# Grove_-_Themocouple_Amplifier_MAX31850K.net
KiCad netlist of a schematic drawn in EAGLE
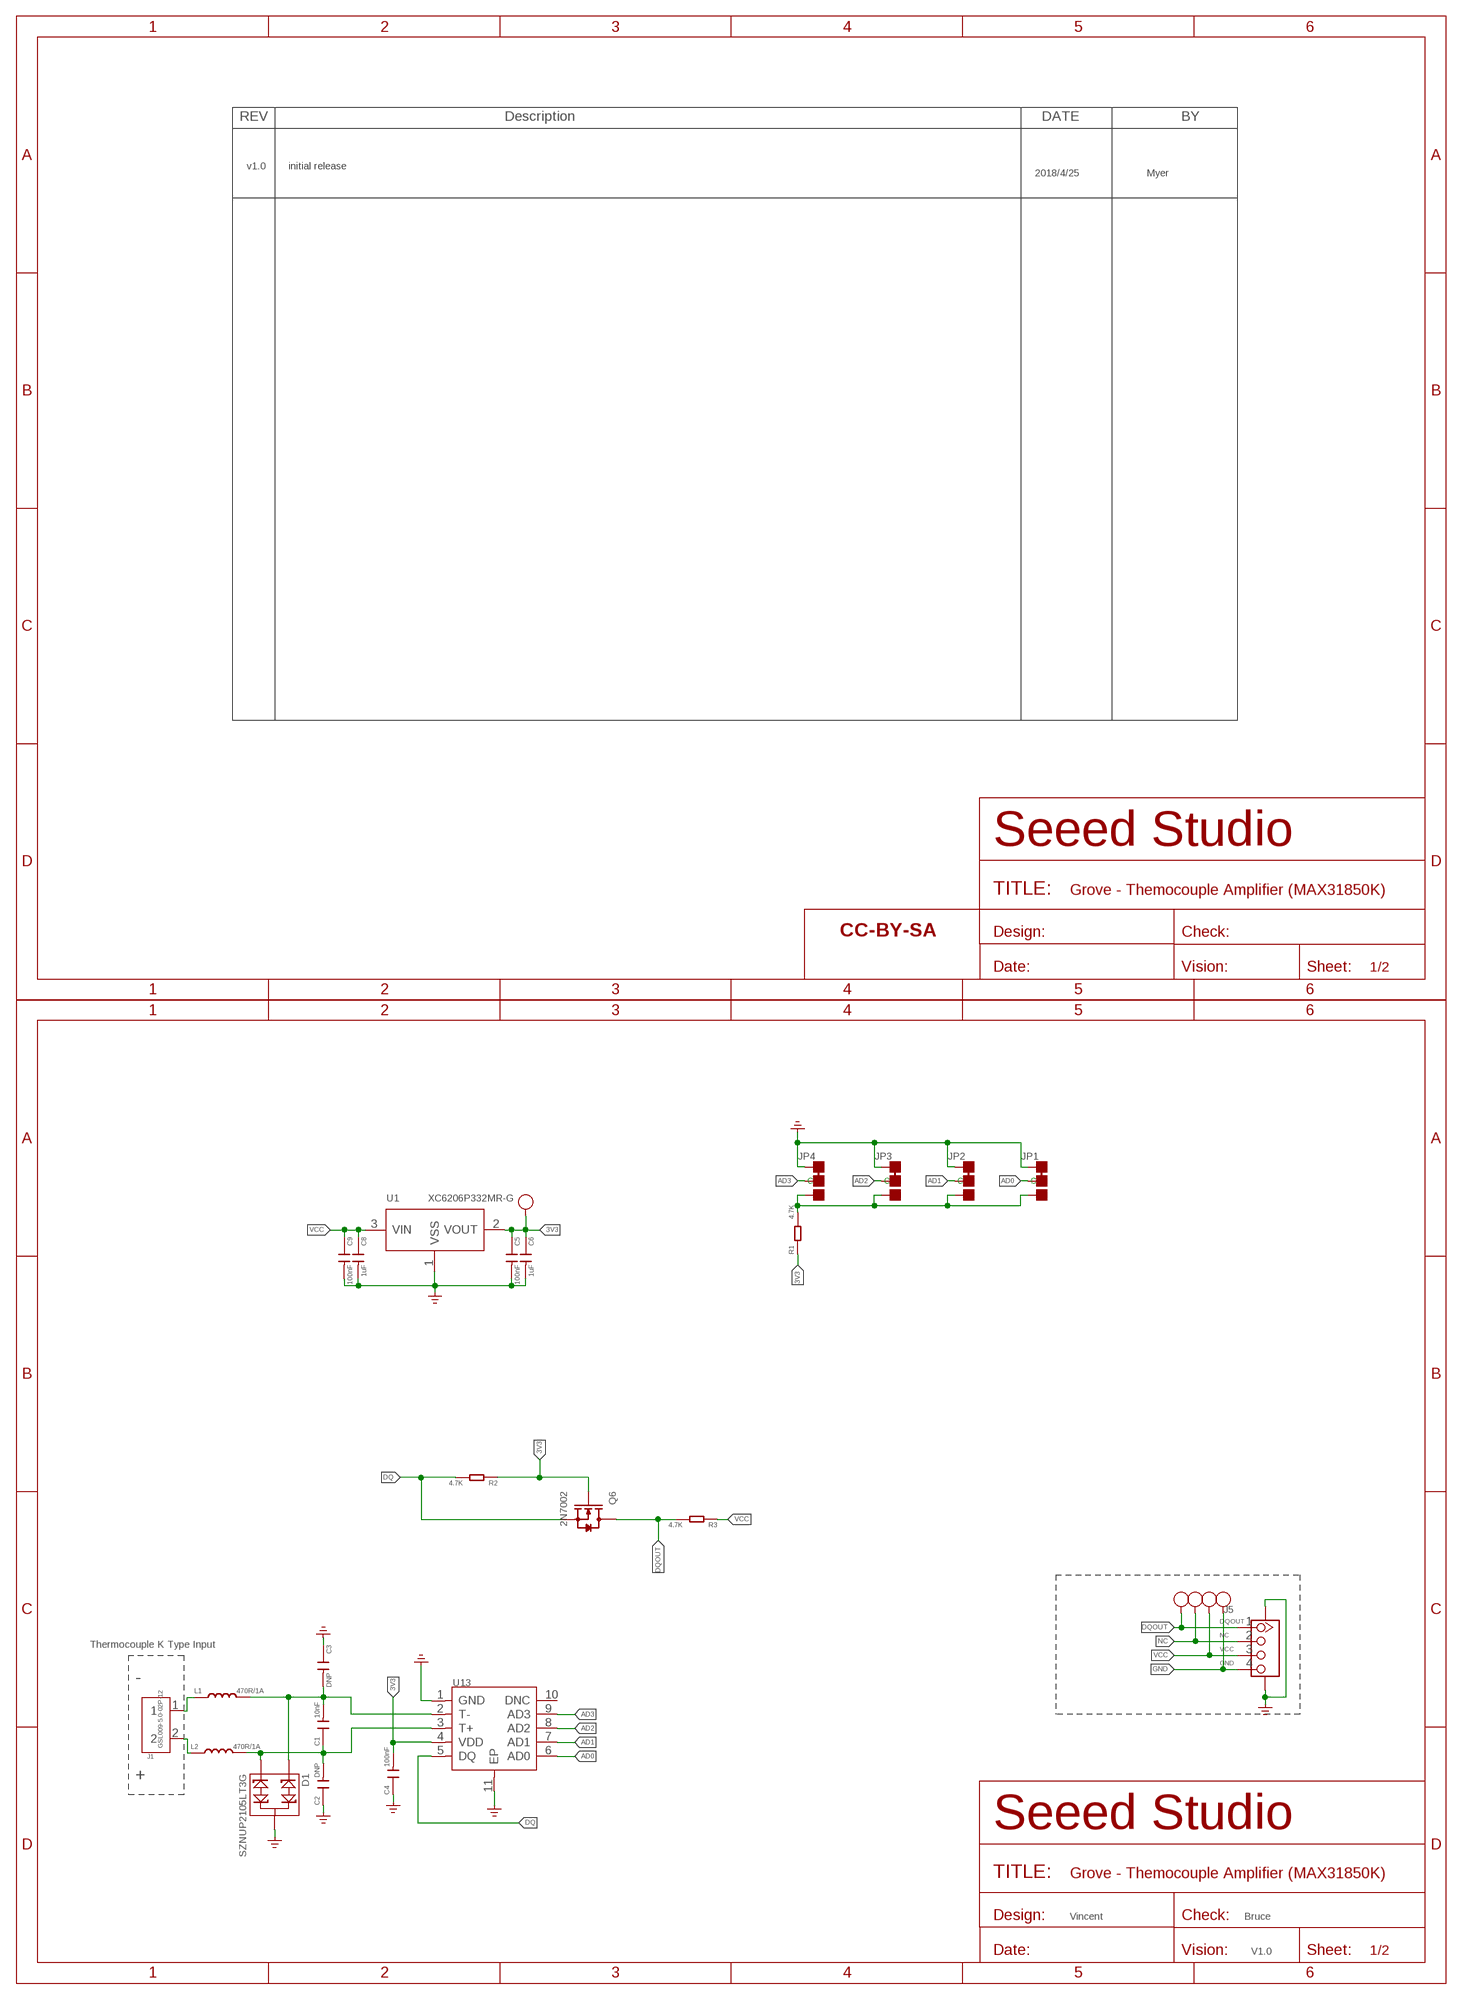
[diagram p0: schematic, sheet 1]
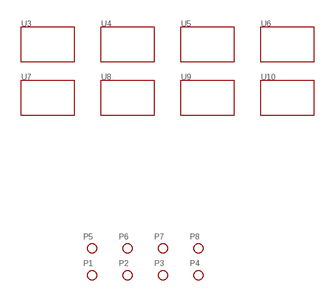
[diagram p1: schematic, sheet 2]

(export (version "E")
  (design (tool "Eeschema 10.0.6"))
  (components
    (comp (ref "C1")
      (value "10nF")
      (footprint "eagle-import:C0805")
      (libsource (lib "eagle-import") (part "C-0805"))
    )
    (comp (ref "C2")
      (value "DNP")
      (footprint "eagle-import:C0603")
      (libsource (lib "eagle-import") (part "C-0603"))
    )
    (comp (ref "C3")
      (value "DNP")
      (footprint "eagle-import:C0603")
      (libsource (lib "eagle-import") (part "C-0603"))
    )
    (comp (ref "C4")
      (value "100nF")
      (footprint "eagle-import:C0603")
      (libsource (lib "eagle-import") (part "C-0603"))
    )
    (comp (ref "C5")
      (value "100nF")
      (footprint "eagle-import:C0603")
      (libsource (lib "eagle-import") (part "C-0603"))
    )
    (comp (ref "C6")
      (value "1uF")
      (footprint "eagle-import:C0603")
      (libsource (lib "eagle-import") (part "C-0603"))
    )
    (comp (ref "C8")
      (value "1uF")
      (footprint "eagle-import:C0603")
      (libsource (lib "eagle-import") (part "C-0603"))
    )
    (comp (ref "C9")
      (value "100nF")
      (footprint "eagle-import:C0603")
      (libsource (lib "eagle-import") (part "C-0603"))
    )
    (comp (ref "D1")
      (value "SZNUP2105LT3G")
      (footprint "eagle-import:SOT-23")
      (libsource (lib "eagle-import") (part "D-TVS-3P'PESD5V0L2BT'"))
    )
    (comp (ref "FR2")
      (value "SEEEDSTUDIO-OPEN-SCH-FRAME")
      (footprint "eagle-import:SEEEDSTUDIO-PCB-FRAME")
      (libsource (lib "eagle-import") (part "SEEEDSTUDIO-OPEN-SCH-FRAME"))
    )
    (comp (ref "GND4")
      (value "TEST-POINT'4545'")
      (footprint "eagle-import:TP-D45MIL")
      (fields (field (name "PARTNO") "DNP"))
      (libsource (lib "eagle-import") (part "TEST-POINT'4545'"))
    )
    (comp (ref "J1")
      (value "GSL009-5.0-02P-12")
      (footprint "eagle-import:2P-5.0-10.6X10X14.8H")
      (libsource (lib "eagle-import") (part "SCREW-TERMINAL-2P'5.0-10.6X10X14.8H'"))
    )
    (comp (ref "J5")
      (value "GROVE-CONNECTOR-SMD'90D'")
      (footprint "eagle-import:HW4-SMD-2.0-90D")
      (libsource (lib "eagle-import") (part "GROVE-CONNECTOR-SMD'90D'"))
    )
    (comp (ref "JP1")
      (value "JP-3P-SHORT")
      (footprint "eagle-import:3P-SMD-SHORT")
      (libsource (lib "eagle-import") (part "JP-3P-SHORT"))
    )
    (comp (ref "JP2")
      (value "JP-3P-SHORT")
      (footprint "eagle-import:3P-SMD-SHORT")
      (libsource (lib "eagle-import") (part "JP-3P-SHORT"))
    )
    (comp (ref "JP3")
      (value "JP-3P-SHORT")
      (footprint "eagle-import:3P-SMD-SHORT")
      (libsource (lib "eagle-import") (part "JP-3P-SHORT"))
    )
    (comp (ref "JP4")
      (value "JP-3P-SHORT")
      (footprint "eagle-import:3P-SMD-SHORT")
      (libsource (lib "eagle-import") (part "JP-3P-SHORT"))
    )
    (comp (ref "L1")
      (value "470R/1A")
      (footprint "eagle-import:L0603")
      (libsource (lib "eagle-import") (part "L-0603"))
    )
    (comp (ref "L2")
      (value "470R/1A")
      (footprint "eagle-import:L0603")
      (libsource (lib "eagle-import") (part "L-0603"))
    )
    (comp (ref "Q6")
      (value "2N7002")
      (footprint "eagle-import:SOT-323")
      (libsource (lib "eagle-import") (part "MOSFET-N+'SI1304BDL'"))
    )
    (comp (ref "R1")
      (value "4.7K")
      (footprint "eagle-import:R0603")
      (libsource (lib "eagle-import") (part "R-0603"))
    )
    (comp (ref "R2")
      (value "4.7K")
      (footprint "eagle-import:R0603")
      (libsource (lib "eagle-import") (part "R-0603"))
    )
    (comp (ref "R3")
      (value "4.7K")
      (footprint "eagle-import:R0603")
      (libsource (lib "eagle-import") (part "R-0603"))
    )
    (comp (ref "SCL")
      (value "TEST-POINT'4545'")
      (footprint "eagle-import:TP-D45MIL")
      (fields (field (name "PARTNO") "DNP"))
      (libsource (lib "eagle-import") (part "TEST-POINT'4545'"))
    )
    (comp (ref "SDA3")
      (value "TEST-POINT'4545'")
      (footprint "eagle-import:TP-D45MIL")
      (fields (field (name "PARTNO") "DNP"))
      (libsource (lib "eagle-import") (part "TEST-POINT'4545'"))
    )
    (comp (ref "SDA4")
      (value "TEST-POINT'4545'")
      (footprint "eagle-import:TP-D45MIL")
      (fields (field (name "PARTNO") "DNP"))
      (libsource (lib "eagle-import") (part "TEST-POINT'4545'"))
    )
    (comp (ref "U1")
      (value "XC6206P332MR-G")
      (footprint "eagle-import:SOT-23")
      (libsource (lib "eagle-import") (part "PMIC-XC6206PMR"))
    )
    (comp (ref "U13")
      (value "CONVERTER-MAX31850")
      (footprint "eagle-import:TDFN10-0.5-3X4MM")
      (libsource (lib "eagle-import") (part "CONVERTER-MAX31850"))
    )
    (comp (ref "VCC1")
      (value "TEST-POINT'4545'")
      (footprint "eagle-import:TP-D45MIL")
      (fields (field (name "PARTNO") "DNP"))
      (libsource (lib "eagle-import") (part "TEST-POINT'4545'"))
    )
    (comp (ref "P1")
      (value "PAD-MARK")
      (footprint "eagle-import:ROUND-MARK-1.0")
      (fields (field (name "PARTNO") "DNP"))
      (libsource (lib "eagle-import") (part "PAD-MARK"))
    )
    (comp (ref "P2")
      (value "PAD-MARK")
      (footprint "eagle-import:ROUND-MARK-1.0")
      (fields (field (name "PARTNO") "DNP"))
      (libsource (lib "eagle-import") (part "PAD-MARK"))
    )
    (comp (ref "P3")
      (value "PAD-MARK")
      (footprint "eagle-import:ROUND-MARK-1.0")
      (fields (field (name "PARTNO") "DNP"))
      (libsource (lib "eagle-import") (part "PAD-MARK"))
    )
    (comp (ref "P4")
      (value "PAD-MARK")
      (footprint "eagle-import:ROUND-MARK-1.0")
      (fields (field (name "PARTNO") "DNP"))
      (libsource (lib "eagle-import") (part "PAD-MARK"))
    )
    (comp (ref "P5")
      (value "PAD-MARK")
      (footprint "eagle-import:ROUND-MARK-1.0")
      (fields (field (name "PARTNO") "DNP"))
      (libsource (lib "eagle-import") (part "PAD-MARK"))
    )
    (comp (ref "P6")
      (value "PAD-MARK")
      (footprint "eagle-import:ROUND-MARK-1.0")
      (fields (field (name "PARTNO") "DNP"))
      (libsource (lib "eagle-import") (part "PAD-MARK"))
    )
    (comp (ref "P7")
      (value "PAD-MARK")
      (footprint "eagle-import:ROUND-MARK-1.0")
      (fields (field (name "PARTNO") "DNP"))
      (libsource (lib "eagle-import") (part "PAD-MARK"))
    )
    (comp (ref "P8")
      (value "PAD-MARK")
      (footprint "eagle-import:ROUND-MARK-1.0")
      (fields (field (name "PARTNO") "DNP"))
      (libsource (lib "eagle-import") (part "PAD-MARK"))
    )
    (comp (ref "U3")
      (value "TWIG'2U'")
      (footprint "eagle-import:GROVE-TEST-PLATFORM")
      (libsource (lib "eagle-import") (part "TWIG'2U'"))
    )
    (comp (ref "U4")
      (value "TWIG'2U'")
      (footprint "eagle-import:GROVE-TEST-PLATFORM")
      (libsource (lib "eagle-import") (part "TWIG'2U'"))
    )
    (comp (ref "U5")
      (value "TWIG'2U'")
      (footprint "eagle-import:GROVE-TEST-PLATFORM")
      (libsource (lib "eagle-import") (part "TWIG'2U'"))
    )
    (comp (ref "U6")
      (value "TWIG'2U'")
      (footprint "eagle-import:GROVE-TEST-PLATFORM")
      (libsource (lib "eagle-import") (part "TWIG'2U'"))
    )
    (comp (ref "U7")
      (value "TWIG'2U'")
      (footprint "eagle-import:GROVE-TEST-PLATFORM")
      (libsource (lib "eagle-import") (part "TWIG'2U'"))
    )
    (comp (ref "U8")
      (value "TWIG'2U'")
      (footprint "eagle-import:GROVE-TEST-PLATFORM")
      (libsource (lib "eagle-import") (part "TWIG'2U'"))
    )
    (comp (ref "U9")
      (value "TWIG'2U'")
      (footprint "eagle-import:GROVE-TEST-PLATFORM")
      (libsource (lib "eagle-import") (part "TWIG'2U'"))
    )
    (comp (ref "U10")
      (value "TWIG'2U'")
      (footprint "eagle-import:GROVE-TEST-PLATFORM")
      (libsource (lib "eagle-import") (part "TWIG'2U'"))
    )
  )
  (nets
    (net (code "1") (name "3V3") (class "Default")
      (node (ref "C4") (pin "2") (pinfunction "2_2") (pintype "passive"))
      (node (ref "C5") (pin "1") (pinfunction "1_1") (pintype "passive"))
      (node (ref "C6") (pin "1") (pinfunction "1_1") (pintype "passive"))
      (node (ref "Q6") (pin "1") (pinfunction "G_1") (pintype "passive"))
      (node (ref "R1") (pin "1") (pinfunction "1_1") (pintype "passive"))
      (node (ref "R2") (pin "1") (pinfunction "1_1") (pintype "passive"))
      (node (ref "SDA3") (pin "T") (pinfunction "T_T") (pintype "bidirectional"))
      (node (ref "U1") (pin "2") (pinfunction "VOUT_2") (pintype "bidirectional"))
      (node (ref "U13") (pin "4") (pinfunction "VDD_4") (pintype "bidirectional"))
    )
    (net (code "2") (name "AD0") (class "Default")
      (node (ref "JP1") (pin "MM") (pinfunction "C_MM") (pintype "bidirectional"))
      (node (ref "U13") (pin "6") (pinfunction "AD0_6") (pintype "bidirectional"))
    )
    (net (code "3") (name "AD1") (class "Default")
      (node (ref "JP2") (pin "MM") (pinfunction "C_MM") (pintype "bidirectional"))
      (node (ref "U13") (pin "7") (pinfunction "AD1_7") (pintype "bidirectional"))
    )
    (net (code "4") (name "AD2") (class "Default")
      (node (ref "JP3") (pin "MM") (pinfunction "C_MM") (pintype "bidirectional"))
      (node (ref "U13") (pin "8") (pinfunction "AD2_8") (pintype "bidirectional"))
    )
    (net (code "5") (name "AD3") (class "Default")
      (node (ref "JP4") (pin "MM") (pinfunction "C_MM") (pintype "bidirectional"))
      (node (ref "U13") (pin "9") (pinfunction "AD3_9") (pintype "bidirectional"))
    )
    (net (code "6") (name "DQ") (class "Default")
      (node (ref "Q6") (pin "2") (pinfunction "S_2") (pintype "passive"))
      (node (ref "R2") (pin "2") (pinfunction "2_2") (pintype "passive"))
      (node (ref "U13") (pin "5") (pinfunction "DQ_5") (pintype "bidirectional"))
    )
    (net (code "7") (name "DQOUT") (class "Default")
      (node (ref "GND4") (pin "T") (pinfunction "T_T") (pintype "bidirectional"))
      (node (ref "J5") (pin "1") (pinfunction "1_1") (pintype "bidirectional"))
      (node (ref "Q6") (pin "3") (pinfunction "D_3") (pintype "passive"))
      (node (ref "R3") (pin "2") (pinfunction "2_2") (pintype "passive"))
    )
    (net (code "8") (name "GND") (class "Default")
      (node (ref "C2") (pin "1") (pinfunction "1_1") (pintype "passive"))
      (node (ref "C3") (pin "1") (pinfunction "1_1") (pintype "passive"))
      (node (ref "C4") (pin "1") (pinfunction "1_1") (pintype "passive"))
      (node (ref "C5") (pin "2") (pinfunction "2_2") (pintype "passive"))
      (node (ref "C6") (pin "2") (pinfunction "2_2") (pintype "passive"))
      (node (ref "C8") (pin "2") (pinfunction "2_2") (pintype "passive"))
      (node (ref "C9") (pin "2") (pinfunction "2_2") (pintype "passive"))
      (node (ref "D1") (pin "3") (pinfunction "3_3") (pintype "bidirectional"))
      (node (ref "J5") (pin "4") (pinfunction "4_4") (pintype "bidirectional"))
      (node (ref "J5") (pin "SS1") (pinfunction "SS1_SS1") (pintype "bidirectional"))
      (node (ref "J5") (pin "SS2") (pinfunction "SS2_SS2") (pintype "bidirectional"))
      (node (ref "JP1") (pin "11") (pinfunction "L_11") (pintype "bidirectional"))
      (node (ref "JP2") (pin "11") (pinfunction "L_11") (pintype "bidirectional"))
      (node (ref "JP3") (pin "11") (pinfunction "L_11") (pintype "bidirectional"))
      (node (ref "JP4") (pin "11") (pinfunction "L_11") (pintype "bidirectional"))
      (node (ref "SCL") (pin "T") (pinfunction "T_T") (pintype "bidirectional"))
      (node (ref "U1") (pin "1") (pinfunction "VSS_1") (pintype "bidirectional"))
      (node (ref "U13") (pin "1") (pinfunction "GND_1") (pintype "bidirectional"))
      (node (ref "U13") (pin "11") (pinfunction "EP_11") (pintype "bidirectional"))
    )
    (net (code "9") (name "NC") (class "Default")
      (node (ref "J5") (pin "2") (pinfunction "2_2") (pintype "bidirectional"))
      (node (ref "VCC1") (pin "T") (pinfunction "T_T") (pintype "bidirectional"))
    )
    (net (code "10") (name "Net-(J1-Pad1)") (class "Default")
      (node (ref "J1") (pin "1") (pinfunction "1_1") (pintype "bidirectional"))
      (node (ref "L1") (pin "1") (pinfunction "1_1") (pintype "passive"))
    )
    (net (code "11") (name "Net-(J1-Pad2)") (class "Default")
      (node (ref "J1") (pin "2") (pinfunction "2_2") (pintype "bidirectional"))
      (node (ref "L2") (pin "1") (pinfunction "1_1") (pintype "passive"))
    )
    (net (code "12") (name "Net-(JP1-R)") (class "Default")
      (node (ref "JP1") (pin "00") (pinfunction "R_00") (pintype "bidirectional"))
      (node (ref "JP2") (pin "00") (pinfunction "R_00") (pintype "bidirectional"))
      (node (ref "JP3") (pin "00") (pinfunction "R_00") (pintype "bidirectional"))
      (node (ref "JP4") (pin "00") (pinfunction "R_00") (pintype "bidirectional"))
      (node (ref "R1") (pin "2") (pinfunction "2_2") (pintype "passive"))
    )
    (net (code "13") (name "Net-(U13-T+)") (class "Default")
      (node (ref "C1") (pin "1") (pinfunction "1_1") (pintype "passive"))
      (node (ref "C2") (pin "2") (pinfunction "2_2") (pintype "passive"))
      (node (ref "D1") (pin "2") (pinfunction "2_2") (pintype "power_in"))
      (node (ref "L2") (pin "2") (pinfunction "2_2") (pintype "passive"))
      (node (ref "U13") (pin "3") (pinfunction "T+_3") (pintype "bidirectional"))
    )
    (net (code "14") (name "Net-(U13-T-)") (class "Default")
      (node (ref "C1") (pin "2") (pinfunction "2_2") (pintype "passive"))
      (node (ref "C3") (pin "2") (pinfunction "2_2") (pintype "passive"))
      (node (ref "D1") (pin "1") (pinfunction "1_1") (pintype "power_in"))
      (node (ref "L1") (pin "2") (pinfunction "2_2") (pintype "passive"))
      (node (ref "U13") (pin "2") (pinfunction "T-_2") (pintype "bidirectional"))
    )
    (net (code "15") (name "VCC") (class "Default")
      (node (ref "C8") (pin "1") (pinfunction "1_1") (pintype "passive"))
      (node (ref "C9") (pin "1") (pinfunction "1_1") (pintype "passive"))
      (node (ref "J5") (pin "3") (pinfunction "3_3") (pintype "bidirectional"))
      (node (ref "R3") (pin "1") (pinfunction "1_1") (pintype "passive"))
      (node (ref "SDA4") (pin "T") (pinfunction "T_T") (pintype "bidirectional"))
      (node (ref "U1") (pin "3") (pinfunction "VIN_3") (pintype "bidirectional"))
    )
    (net (code "16") (name "unconnected-(U13-DNC-Pad10)") (class "Default")
      (node (ref "U13") (pin "10") (pinfunction "DNC_10") (pintype "bidirectional"))
    )
  )
)
